# 6_channel_remote.net
KiCad netlist of a schematic drawn in EAGLE
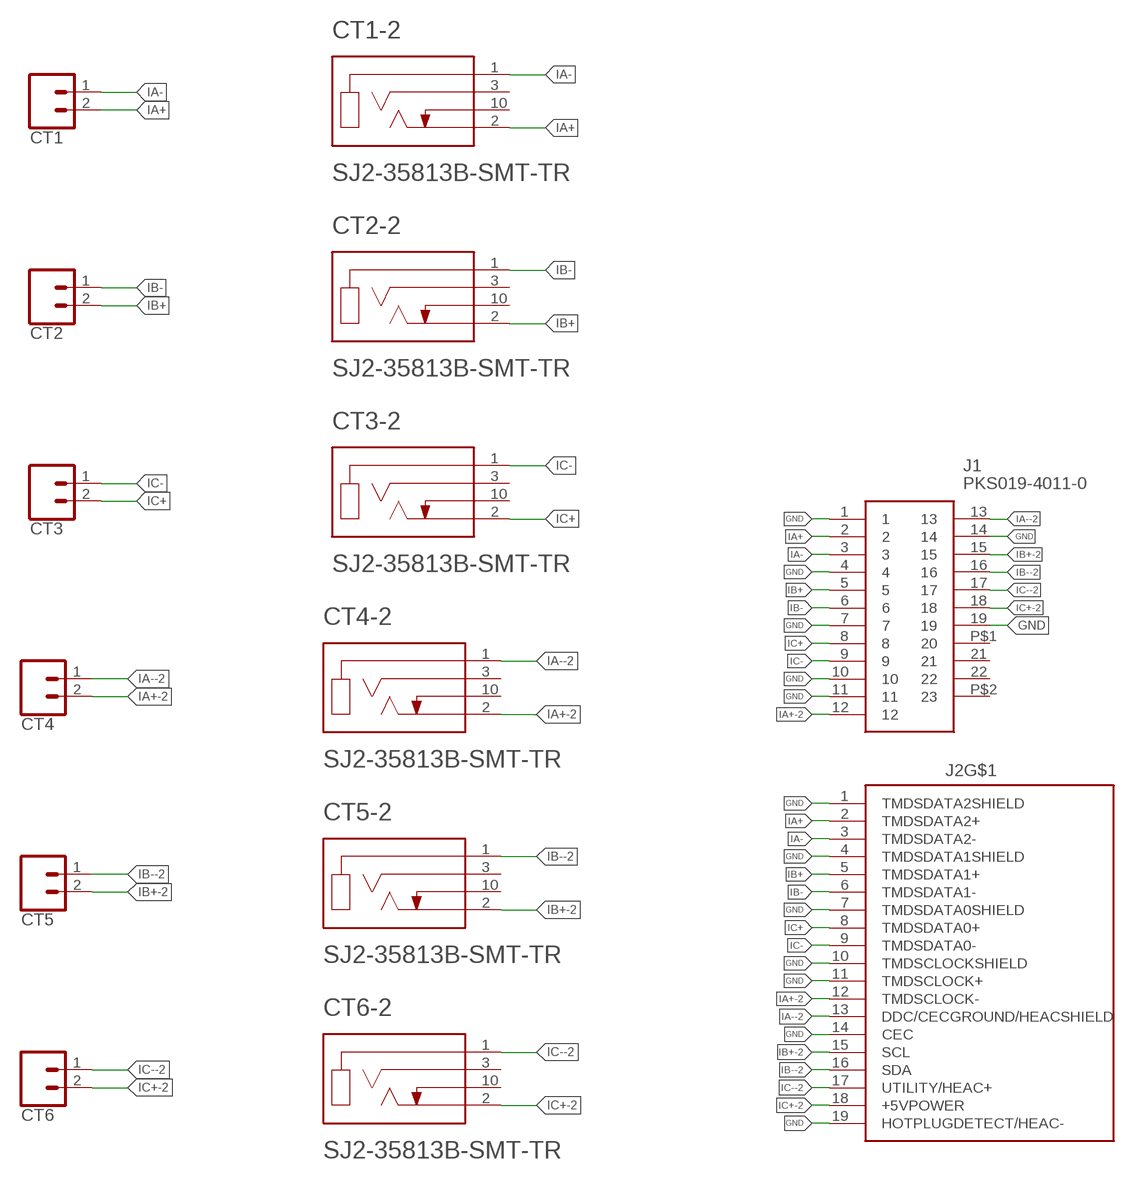
[diagram p0: schematic, sheet 1]

(export (version "E")
  (design (tool "Eeschema 10.0.6"))
  (components
    (comp (ref "CT1")
      (value "CONN_023.5MM")
      (footprint "eagle-import:SCREWTERMINAL-3.5MM-2")
      (libsource (lib "eagle-import") (part "CONN_023.5MM"))
    )
    (comp (ref "CT1-2")
      (value "SJ2-35813B-SMT-TR")
      (footprint "eagle-import:CUI_SJ2-35813B-SMT-TR")
      (fields (field (name "MANUFACTURER") "CUI"))
      (libsource (lib "eagle-import") (part "SJ2-35813B-SMT-TR"))
    )
    (comp (ref "CT2")
      (value "CONN_023.5MM")
      (footprint "eagle-import:SCREWTERMINAL-3.5MM-2")
      (libsource (lib "eagle-import") (part "CONN_023.5MM"))
    )
    (comp (ref "CT2-2")
      (value "SJ2-35813B-SMT-TR")
      (footprint "eagle-import:CUI_SJ2-35813B-SMT-TR")
      (fields (field (name "MANUFACTURER") "CUI"))
      (libsource (lib "eagle-import") (part "SJ2-35813B-SMT-TR"))
    )
    (comp (ref "CT3")
      (value "CONN_023.5MM")
      (footprint "eagle-import:SCREWTERMINAL-3.5MM-2")
      (libsource (lib "eagle-import") (part "CONN_023.5MM"))
    )
    (comp (ref "CT3-2")
      (value "SJ2-35813B-SMT-TR")
      (footprint "eagle-import:CUI_SJ2-35813B-SMT-TR")
      (fields (field (name "MANUFACTURER") "CUI"))
      (libsource (lib "eagle-import") (part "SJ2-35813B-SMT-TR"))
    )
    (comp (ref "CT4")
      (value "CONN_023.5MM")
      (footprint "eagle-import:SCREWTERMINAL-3.5MM-2")
      (libsource (lib "eagle-import") (part "CONN_023.5MM"))
    )
    (comp (ref "CT4-2")
      (value "SJ2-35813B-SMT-TR")
      (footprint "eagle-import:CUI_SJ2-35813B-SMT-TR")
      (fields (field (name "MANUFACTURER") "CUI"))
      (libsource (lib "eagle-import") (part "SJ2-35813B-SMT-TR"))
    )
    (comp (ref "CT5")
      (value "CONN_023.5MM")
      (footprint "eagle-import:SCREWTERMINAL-3.5MM-2")
      (libsource (lib "eagle-import") (part "CONN_023.5MM"))
    )
    (comp (ref "CT5-2")
      (value "SJ2-35813B-SMT-TR")
      (footprint "eagle-import:CUI_SJ2-35813B-SMT-TR")
      (fields (field (name "MANUFACTURER") "CUI"))
      (libsource (lib "eagle-import") (part "SJ2-35813B-SMT-TR"))
    )
    (comp (ref "CT6")
      (value "CONN_023.5MM")
      (footprint "eagle-import:SCREWTERMINAL-3.5MM-2")
      (libsource (lib "eagle-import") (part "CONN_023.5MM"))
    )
    (comp (ref "CT6-2")
      (value "SJ2-35813B-SMT-TR")
      (footprint "eagle-import:CUI_SJ2-35813B-SMT-TR")
      (fields (field (name "MANUFACTURER") "CUI"))
      (libsource (lib "eagle-import") (part "SJ2-35813B-SMT-TR"))
    )
    (comp (ref "J1")
      (value "PKS019-4011-0")
      (footprint "eagle-import:PKS01940110")
      (fields (field (name "MOUSER_PART_NUMBER") "945-PKS019-4011-0"))
      (libsource (lib "eagle-import") (part "PKS019-4011-0"))
    )
    (comp (ref "J2")
      (value "685119136923")
      (footprint "eagle-import:685119136923")
      (libsource (lib "eagle-import") (part "685119136923"))
    )
  )
  (nets
    (net (code "1") (name "GND") (class "Default")
      (node (ref "J1") (pin "1") (pinfunction "1_1") (pintype "bidirectional"))
      (node (ref "J1") (pin "10") (pinfunction "10_10") (pintype "bidirectional"))
      (node (ref "J1") (pin "11") (pinfunction "11_11") (pintype "bidirectional"))
      (node (ref "J1") (pin "14") (pinfunction "14_14") (pintype "bidirectional"))
      (node (ref "J1") (pin "19") (pinfunction "19_19") (pintype "bidirectional"))
      (node (ref "J1") (pin "4") (pinfunction "4_4") (pintype "bidirectional"))
      (node (ref "J1") (pin "7") (pinfunction "7_7") (pintype "bidirectional"))
      (node (ref "J2") (pin "1") (pinfunction "TMDSDATA2SHIELD_1") (pintype "passive"))
      (node (ref "J2") (pin "10") (pinfunction "TMDSCLOCKSHIELD_10") (pintype "passive"))
      (node (ref "J2") (pin "11") (pinfunction "TMDSCLOCK+_11") (pintype "passive"))
      (node (ref "J2") (pin "14") (pinfunction "CEC_14") (pintype "passive"))
      (node (ref "J2") (pin "19") (pinfunction "HOTPLUGDETECT/HEAC-_19") (pintype "passive"))
      (node (ref "J2") (pin "4") (pinfunction "TMDSDATA1SHIELD_4") (pintype "passive"))
      (node (ref "J2") (pin "7") (pinfunction "TMDSDATA0SHIELD_7") (pintype "passive"))
    )
    (net (code "2") (name "IA+") (class "Default")
      (node (ref "CT1") (pin "2") (pinfunction "2_2") (pintype "passive"))
      (node (ref "CT1-2") (pin "2") (pinfunction "TIP_2") (pintype "passive"))
      (node (ref "J1") (pin "2") (pinfunction "2_2") (pintype "bidirectional"))
      (node (ref "J2") (pin "2") (pinfunction "TMDSDATA2+_2") (pintype "passive"))
    )
    (net (code "3") (name "IA+-2") (class "Default")
      (node (ref "CT4") (pin "2") (pinfunction "2_2") (pintype "passive"))
      (node (ref "CT4-2") (pin "2") (pinfunction "TIP_2") (pintype "passive"))
      (node (ref "J1") (pin "12") (pinfunction "12_12") (pintype "bidirectional"))
      (node (ref "J2") (pin "12") (pinfunction "TMDSCLOCK-_12") (pintype "passive"))
    )
    (net (code "4") (name "IA-") (class "Default")
      (node (ref "CT1") (pin "1") (pinfunction "1_1") (pintype "passive"))
      (node (ref "CT1-2") (pin "1") (pinfunction "SLEEVE_1") (pintype "passive"))
      (node (ref "J1") (pin "3") (pinfunction "3_3") (pintype "bidirectional"))
      (node (ref "J2") (pin "3") (pinfunction "TMDSDATA2-_3") (pintype "passive"))
    )
    (net (code "5") (name "IA--2") (class "Default")
      (node (ref "CT4") (pin "1") (pinfunction "1_1") (pintype "passive"))
      (node (ref "CT4-2") (pin "1") (pinfunction "SLEEVE_1") (pintype "passive"))
      (node (ref "J1") (pin "13") (pinfunction "13_13") (pintype "bidirectional"))
      (node (ref "J2") (pin "13") (pinfunction "DDC/CECGROUND/HEACSHIELD_13") (pintype "passive"))
    )
    (net (code "6") (name "IB+") (class "Default")
      (node (ref "CT2") (pin "2") (pinfunction "2_2") (pintype "passive"))
      (node (ref "CT2-2") (pin "2") (pinfunction "TIP_2") (pintype "passive"))
      (node (ref "J1") (pin "5") (pinfunction "5_5") (pintype "bidirectional"))
      (node (ref "J2") (pin "5") (pinfunction "TMDSDATA1+_5") (pintype "passive"))
    )
    (net (code "7") (name "IB+-2") (class "Default")
      (node (ref "CT5") (pin "2") (pinfunction "2_2") (pintype "passive"))
      (node (ref "CT5-2") (pin "2") (pinfunction "TIP_2") (pintype "passive"))
      (node (ref "J1") (pin "15") (pinfunction "15_15") (pintype "bidirectional"))
      (node (ref "J2") (pin "15") (pinfunction "SCL_15") (pintype "passive"))
    )
    (net (code "8") (name "IB-") (class "Default")
      (node (ref "CT2") (pin "1") (pinfunction "1_1") (pintype "passive"))
      (node (ref "CT2-2") (pin "1") (pinfunction "SLEEVE_1") (pintype "passive"))
      (node (ref "J1") (pin "6") (pinfunction "6_6") (pintype "bidirectional"))
      (node (ref "J2") (pin "6") (pinfunction "TMDSDATA1-_6") (pintype "passive"))
    )
    (net (code "9") (name "IB--2") (class "Default")
      (node (ref "CT5") (pin "1") (pinfunction "1_1") (pintype "passive"))
      (node (ref "CT5-2") (pin "1") (pinfunction "SLEEVE_1") (pintype "passive"))
      (node (ref "J1") (pin "16") (pinfunction "16_16") (pintype "bidirectional"))
      (node (ref "J2") (pin "16") (pinfunction "SDA_16") (pintype "passive"))
    )
    (net (code "10") (name "IC+") (class "Default")
      (node (ref "CT3") (pin "2") (pinfunction "2_2") (pintype "passive"))
      (node (ref "CT3-2") (pin "2") (pinfunction "TIP_2") (pintype "passive"))
      (node (ref "J1") (pin "8") (pinfunction "8_8") (pintype "bidirectional"))
      (node (ref "J2") (pin "8") (pinfunction "TMDSDATA0+_8") (pintype "passive"))
    )
    (net (code "11") (name "IC+-2") (class "Default")
      (node (ref "CT6") (pin "2") (pinfunction "2_2") (pintype "passive"))
      (node (ref "CT6-2") (pin "2") (pinfunction "TIP_2") (pintype "passive"))
      (node (ref "J1") (pin "18") (pinfunction "18_18") (pintype "bidirectional"))
      (node (ref "J2") (pin "18") (pinfunction "+5VPOWER_18") (pintype "power_in"))
    )
    (net (code "12") (name "IC-") (class "Default")
      (node (ref "CT3") (pin "1") (pinfunction "1_1") (pintype "passive"))
      (node (ref "CT3-2") (pin "1") (pinfunction "SLEEVE_1") (pintype "passive"))
      (node (ref "J1") (pin "9") (pinfunction "9_9") (pintype "bidirectional"))
      (node (ref "J2") (pin "9") (pinfunction "TMDSDATA0-_9") (pintype "passive"))
    )
    (net (code "13") (name "IC--2") (class "Default")
      (node (ref "CT6") (pin "1") (pinfunction "1_1") (pintype "passive"))
      (node (ref "CT6-2") (pin "1") (pinfunction "SLEEVE_1") (pintype "passive"))
      (node (ref "J1") (pin "17") (pinfunction "17_17") (pintype "bidirectional"))
      (node (ref "J2") (pin "17") (pinfunction "UTILITY/HEAC+_17") (pintype "passive"))
    )
    (net (code "14") (name "unconnected-(CT1-2-RING-Pad3)") (class "Default")
      (node (ref "CT1-2") (pin "3") (pinfunction "RING_3") (pintype "passive"))
    )
    (net (code "15") (name "unconnected-(CT1-2-TIP_SWITCH-Pad10)") (class "Default")
      (node (ref "CT1-2") (pin "10") (pinfunction "TIP_SWITCH_10") (pintype "passive"))
    )
    (net (code "16") (name "unconnected-(CT2-2-RING-Pad3)") (class "Default")
      (node (ref "CT2-2") (pin "3") (pinfunction "RING_3") (pintype "passive"))
    )
    (net (code "17") (name "unconnected-(CT2-2-TIP_SWITCH-Pad10)") (class "Default")
      (node (ref "CT2-2") (pin "10") (pinfunction "TIP_SWITCH_10") (pintype "passive"))
    )
    (net (code "18") (name "unconnected-(CT3-2-RING-Pad3)") (class "Default")
      (node (ref "CT3-2") (pin "3") (pinfunction "RING_3") (pintype "passive"))
    )
    (net (code "19") (name "unconnected-(CT3-2-TIP_SWITCH-Pad10)") (class "Default")
      (node (ref "CT3-2") (pin "10") (pinfunction "TIP_SWITCH_10") (pintype "passive"))
    )
    (net (code "20") (name "unconnected-(CT4-2-RING-Pad3)") (class "Default")
      (node (ref "CT4-2") (pin "3") (pinfunction "RING_3") (pintype "passive"))
    )
    (net (code "21") (name "unconnected-(CT4-2-TIP_SWITCH-Pad10)") (class "Default")
      (node (ref "CT4-2") (pin "10") (pinfunction "TIP_SWITCH_10") (pintype "passive"))
    )
    (net (code "22") (name "unconnected-(CT5-2-RING-Pad3)") (class "Default")
      (node (ref "CT5-2") (pin "3") (pinfunction "RING_3") (pintype "passive"))
    )
    (net (code "23") (name "unconnected-(CT5-2-TIP_SWITCH-Pad10)") (class "Default")
      (node (ref "CT5-2") (pin "10") (pinfunction "TIP_SWITCH_10") (pintype "passive"))
    )
    (net (code "24") (name "unconnected-(CT6-2-RING-Pad3)") (class "Default")
      (node (ref "CT6-2") (pin "3") (pinfunction "RING_3") (pintype "passive"))
    )
    (net (code "25") (name "unconnected-(CT6-2-TIP_SWITCH-Pad10)") (class "Default")
      (node (ref "CT6-2") (pin "10") (pinfunction "TIP_SWITCH_10") (pintype "passive"))
    )
    (net (code "26") (name "unconnected-(J1-20-PadP$1)") (class "Default")
      (node (ref "J1") (pin "P$1") (pinfunction "20_P$1") (pintype "bidirectional"))
    )
    (net (code "27") (name "unconnected-(J1-23-PadP$2)") (class "Default")
      (node (ref "J1") (pin "P$2") (pinfunction "23_P$2") (pintype "bidirectional"))
    )
    (net (code "28") (name "unconnected-(J1-Pad21)") (class "Default")
      (node (ref "J1") (pin "21") (pinfunction "21_21") (pintype "bidirectional"))
    )
    (net (code "29") (name "unconnected-(J1-Pad22)") (class "Default")
      (node (ref "J1") (pin "22") (pinfunction "22_22") (pintype "bidirectional"))
    )
  )
)
